# DualUSB2_0_HDR.net
KiCad netlist of a schematic drawn in Altium Designer
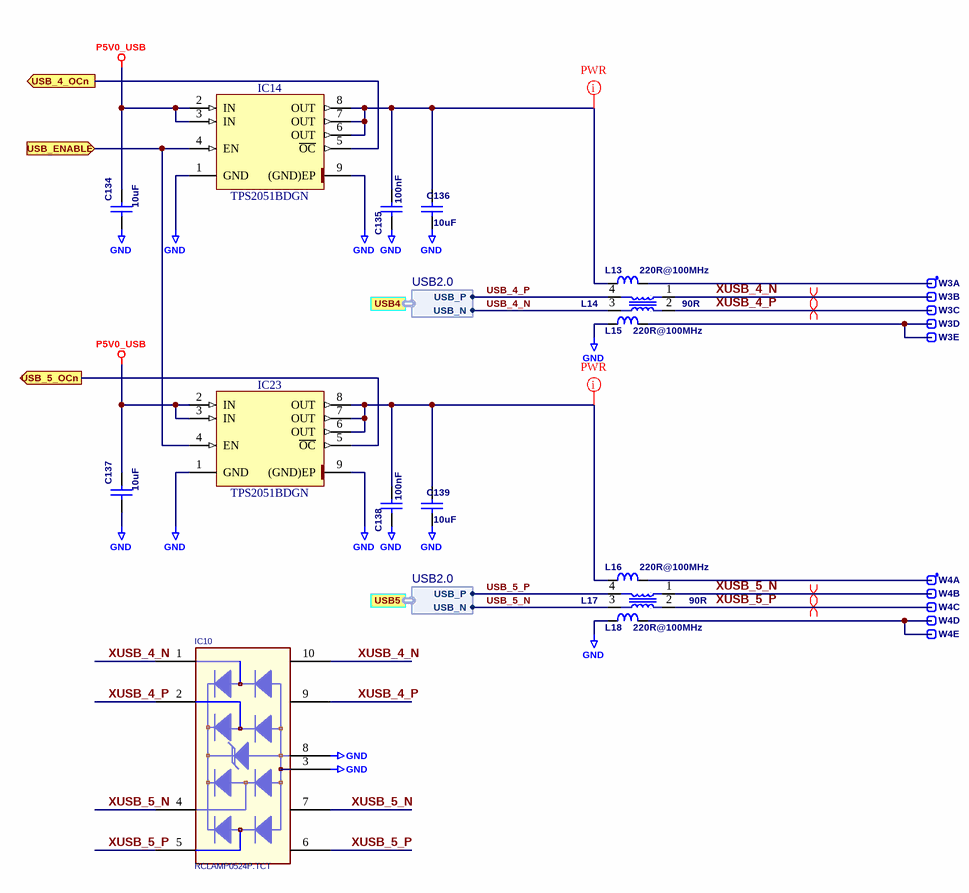
[diagram p0: DualUSB2.0_HDR.SchDoc]

(export (version "E")
  (design (tool "Eeschema 10.0.6"))
  (components
    (comp (ref "C134")
      (value "10uF")
      (footprint "CAPC2012X135N")
      (description "Non-polarised capacitor")
      (fields
        (field (name "PART NUMBER") "CC0805_10UF_10V_10%_X7R")
        (field (name "VOLTAGE") "10V")
        (field (name "AUTHOR") "CERN DEM JLC")
      )
      (libsource (lib "Capacitors") (part "Capacitor - non polarized"))
    )
    (comp (ref "C135")
      (value "100nF")
      (footprint "CAPC1005X55N")
      (description "Non-polarised capacitor")
      (fields
        (field (name "PART NUMBER") "CC0402_100NF_16V_10%_X7R")
        (field (name "VOLTAGE") "16V")
        (field (name "AUTHOR") "CERN DEM JLC")
      )
      (libsource (lib "Capacitors") (part "Capacitor - non polarized"))
    )
    (comp (ref "C136")
      (value "10uF")
      (footprint "CAPC2012X135N")
      (description "Non-polarised capacitor")
      (fields
        (field (name "PART NUMBER") "CC0805_10UF_10V_10%_X7R")
        (field (name "VOLTAGE") "10V")
        (field (name "AUTHOR") "CERN DEM JLC")
      )
      (libsource (lib "Capacitors") (part "Capacitor - non polarized"))
    )
    (comp (ref "C137")
      (value "10uF")
      (footprint "CAPC2012X135N")
      (description "Non-polarised capacitor")
      (fields
        (field (name "PART NUMBER") "CC0805_10UF_10V_10%_X7R")
        (field (name "VOLTAGE") "10V")
        (field (name "AUTHOR") "CERN DEM JLC")
      )
      (libsource (lib "Capacitors") (part "Capacitor - non polarized"))
    )
    (comp (ref "C138")
      (value "100nF")
      (footprint "CAPC1005X55N")
      (description "Non-polarised capacitor")
      (fields
        (field (name "PART NUMBER") "CC0402_100NF_16V_10%_X7R")
        (field (name "VOLTAGE") "16V")
        (field (name "AUTHOR") "CERN DEM JLC")
      )
      (libsource (lib "Capacitors") (part "Capacitor - non polarized"))
    )
    (comp (ref "C139")
      (value "10uF")
      (footprint "CAPC2012X135N")
      (description "Non-polarised capacitor")
      (fields
        (field (name "PART NUMBER") "CC0805_10UF_10V_10%_X7R")
        (field (name "VOLTAGE") "10V")
        (field (name "AUTHOR") "CERN DEM JLC")
      )
      (libsource (lib "Capacitors") (part "Capacitor - non polarized"))
    )
    (comp (ref "IC10")
      (value "RCLAMP0524P.TCT")
      (description "DIODE,RCLAMP0524P,SEMTECH")
      (libsource (lib "LIBRARY_SCH") (part "D_TVS_RCLAMP0524P"))
    )
    (comp (ref "IC14")
      (value "TPS2051BDGN")
      (footprint "SOP65P490X110-9N-R157X189")
      (description "One Channel, Current-Limited, Power-Distribution Switches")
      (fields (field (name "MANUFACTURER") "TEXAS INSTRUMENTS") (field (name "AUTHOR") "CERN DEM BC"))
      (libsource (lib "ICs And Semiconductors") (part "TPS2051BDGN"))
    )
    (comp (ref "IC23")
      (value "TPS2051BDGN")
      (footprint "SOP65P490X110-9N-R157X189")
      (description "One Channel, Current-Limited, Power-Distribution Switches")
      (fields (field (name "MANUFACTURER") "TEXAS INSTRUMENTS") (field (name "AUTHOR") "CERN DEM BC"))
      (libsource (lib "ICs And Semiconductors") (part "TPS2051BDGN"))
    )
    (comp (ref "L13")
      (value "220R@100MHz")
      (footprint "INDC2012X105N")
      (description "Inductor")
      (fields
        (field (name "PART NUMBER") "IND0805_MURATA_BLM21PG221SN1D")
        (field (name "POWER") "2A")
        (field (name "AUTHOR") "CERN DEM JLC")
      )
      (libsource (lib "Inductors & Transformers") (part "Inductor"))
    )
    (comp (ref "L14")
      (value "90R")
      (footprint "DLSCM0805")
      (description "Common Mode Choke 90R")
      (fields (field (name "Comment") "DLSCM0805-900M or DLW21SN900SQ2L"))
      (libsource (lib "LIBRARY_SCH") (part "L_CMC_DLSCM0805_90R"))
    )
    (comp (ref "L15")
      (value "220R@100MHz")
      (footprint "INDC2012X105N")
      (description "Inductor")
      (fields
        (field (name "PART NUMBER") "IND0805_MURATA_BLM21PG221SN1D")
        (field (name "POWER") "2A")
        (field (name "AUTHOR") "CERN DEM JLC")
      )
      (libsource (lib "Inductors & Transformers") (part "Inductor"))
    )
    (comp (ref "L16")
      (value "220R@100MHz")
      (footprint "INDC2012X105N")
      (description "Inductor")
      (fields
        (field (name "PART NUMBER") "IND0805_MURATA_BLM21PG221SN1D")
        (field (name "POWER") "2A")
        (field (name "AUTHOR") "CERN DEM JLC")
      )
      (libsource (lib "Inductors & Transformers") (part "Inductor"))
    )
    (comp (ref "L17")
      (value "90R")
      (footprint "DLSCM0805")
      (description "Common Mode Choke 90R")
      (fields (field (name "Comment") "DLSCM0805-900M or DLW21SN900SQ2L"))
      (libsource (lib "LIBRARY_SCH") (part "L_CMC_DLSCM0805_90R"))
    )
    (comp (ref "L18")
      (value "220R@100MHz")
      (footprint "INDC2012X105N")
      (description "Inductor")
      (fields
        (field (name "PART NUMBER") "IND0805_MURATA_BLM21PG221SN1D")
        (field (name "POWER") "2A")
        (field (name "AUTHOR") "CERN DEM JLC")
      )
      (libsource (lib "Inductors & Transformers") (part "Inductor"))
    )
    (comp (ref "W3")
      (value "Header 5")
      (footprint "SAMTEC_MTLW-105-07-L-S-250")
      (description "5 Mini Wire-Wrap Contact Strip Header")
      (fields
        (field (name "PART NUMBER") "SAMTEC_MTLW-105-07-L-S-250")
        (field (name "MANUFACTURER") "SAMTEC")
        (field (name "AUTHOR") "CERN DEM JLC")
      )
      (libsource (lib "Connectors") (part "Wire-Wrap Contact x5"))
    )
    (comp (ref "W4")
      (value "Header 5")
      (footprint "SAMTEC_MTLW-105-07-L-S-250")
      (description "5 Mini Wire-Wrap Contact Strip Header")
      (fields
        (field (name "PART NUMBER") "SAMTEC_MTLW-105-07-L-S-250")
        (field (name "MANUFACTURER") "SAMTEC")
        (field (name "AUTHOR") "CERN DEM JLC")
      )
      (libsource (lib "Connectors") (part "Wire-Wrap Contact x5"))
    )
  )
  (nets
    (net (code "2") (name "/USB_4_N") (class "Default")
      (node (ref "L14") (pin "3") (pinfunction "3_3") (pintype "passive"))
    )
    (net (code "3") (name "/USB_4_OCn") (class "Default")
      (node (ref "IC14") (pin "5") (pinfunction "~{OC}_5") (pintype "output"))
    )
    (net (code "4") (name "/USB_4_P") (class "Default")
      (node (ref "L14") (pin "4") (pinfunction "4_4") (pintype "passive"))
    )
    (net (code "5") (name "/USB_5_N") (class "Default")
      (node (ref "L17") (pin "3") (pinfunction "3_3") (pintype "passive"))
    )
    (net (code "6") (name "/USB_5_OCn") (class "Default")
      (node (ref "IC23") (pin "5") (pinfunction "~{OC}_5") (pintype "output"))
    )
    (net (code "7") (name "/USB_5_P") (class "Default")
      (node (ref "L17") (pin "4") (pinfunction "4_4") (pintype "passive"))
    )
    (net (code "8") (name "/USB_ENABLE") (class "Default")
      (node (ref "IC14") (pin "4") (pinfunction "EN_4") (pintype "input"))
      (node (ref "IC23") (pin "4") (pinfunction "EN_4") (pintype "input"))
    )
    (net (code "9") (name "/XUSB_4_N") (class "Default")
      (node (ref "IC10") (pin "1") (pinfunction "1_1") (pintype "passive"))
      (node (ref "IC10") (pin "10") (pinfunction "10_10") (pintype "passive"))
      (node (ref "L14") (pin "1") (pinfunction "1_1") (pintype "passive"))
      (node (ref "W3") (pin "2") (pinfunction "2_2") (pintype "bidirectional"))
    )
    (net (code "10") (name "/XUSB_4_P") (class "Default")
      (node (ref "IC10") (pin "2") (pinfunction "2_2") (pintype "passive"))
      (node (ref "IC10") (pin "9") (pinfunction "9_9") (pintype "passive"))
      (node (ref "L14") (pin "2") (pinfunction "2_2") (pintype "passive"))
      (node (ref "W3") (pin "3") (pinfunction "3_3") (pintype "bidirectional"))
    )
    (net (code "11") (name "/XUSB_5_N") (class "Default")
      (node (ref "IC10") (pin "4") (pinfunction "4_4") (pintype "passive"))
      (node (ref "IC10") (pin "7") (pinfunction "7_7") (pintype "passive"))
      (node (ref "L17") (pin "1") (pinfunction "1_1") (pintype "passive"))
      (node (ref "W4") (pin "2") (pinfunction "2_2") (pintype "bidirectional"))
    )
    (net (code "12") (name "/XUSB_5_P") (class "Default")
      (node (ref "IC10") (pin "5") (pinfunction "5_5") (pintype "passive"))
      (node (ref "IC10") (pin "6") (pinfunction "6_6") (pintype "passive"))
      (node (ref "L17") (pin "2") (pinfunction "2_2") (pintype "passive"))
      (node (ref "W4") (pin "3") (pinfunction "3_3") (pintype "bidirectional"))
    )
    (net (code "14") (name "GND") (class "Default")
      (node (ref "C134") (pin "1") (pinfunction "1_1") (pintype "passive"))
      (node (ref "C135") (pin "1") (pinfunction "1_1") (pintype "passive"))
      (node (ref "C136") (pin "1") (pinfunction "1_1") (pintype "passive"))
      (node (ref "C137") (pin "1") (pinfunction "1_1") (pintype "passive"))
      (node (ref "C138") (pin "1") (pinfunction "1_1") (pintype "passive"))
      (node (ref "C139") (pin "1") (pinfunction "1_1") (pintype "passive"))
      (node (ref "IC10") (pin "3") (pinfunction "3_3") (pintype "passive"))
      (node (ref "IC10") (pin "8") (pinfunction "8_8") (pintype "passive"))
      (node (ref "IC14") (pin "1") (pinfunction "GND_1") (pintype "power_in"))
      (node (ref "IC14") (pin "9") (pinfunction "(GND)EP_9") (pintype "power_in"))
      (node (ref "IC23") (pin "1") (pinfunction "GND_1") (pintype "power_in"))
      (node (ref "IC23") (pin "9") (pinfunction "(GND)EP_9") (pintype "power_in"))
      (node (ref "L15") (pin "1") (pinfunction "1_1") (pintype "passive"))
      (node (ref "L18") (pin "1") (pinfunction "1_1") (pintype "passive"))
    )
    (net (code "15") (name "Net-(C135-Pad2)") (class "Default")
      (node (ref "C135") (pin "2") (pinfunction "2_2") (pintype "passive"))
      (node (ref "C136") (pin "2") (pinfunction "2_2") (pintype "passive"))
      (node (ref "IC14") (pin "6") (pinfunction "OUT_6") (pintype "output"))
      (node (ref "IC14") (pin "7") (pinfunction "OUT_7") (pintype "output"))
      (node (ref "IC14") (pin "8") (pinfunction "OUT_8") (pintype "output"))
      (node (ref "L13") (pin "1") (pinfunction "1_1") (pintype "passive"))
    )
    (net (code "16") (name "Net-(C138-Pad2)") (class "Default")
      (node (ref "C138") (pin "2") (pinfunction "2_2") (pintype "passive"))
      (node (ref "C139") (pin "2") (pinfunction "2_2") (pintype "passive"))
      (node (ref "IC23") (pin "6") (pinfunction "OUT_6") (pintype "output"))
      (node (ref "IC23") (pin "7") (pinfunction "OUT_7") (pintype "output"))
      (node (ref "IC23") (pin "8") (pinfunction "OUT_8") (pintype "output"))
      (node (ref "L16") (pin "1") (pinfunction "1_1") (pintype "passive"))
    )
    (net (code "17") (name "Net-(L13-Pad2)") (class "Default")
      (node (ref "L13") (pin "2") (pinfunction "2_2") (pintype "passive"))
      (node (ref "W3") (pin "1") (pinfunction "1_1") (pintype "bidirectional"))
    )
    (net (code "18") (name "Net-(L15-Pad2)") (class "Default")
      (node (ref "L15") (pin "2") (pinfunction "2_2") (pintype "passive"))
      (node (ref "W3") (pin "4") (pinfunction "4_4") (pintype "bidirectional"))
      (node (ref "W3") (pin "5") (pinfunction "5_5") (pintype "bidirectional"))
    )
    (net (code "19") (name "Net-(L16-Pad2)") (class "Default")
      (node (ref "L16") (pin "2") (pinfunction "2_2") (pintype "passive"))
      (node (ref "W4") (pin "1") (pinfunction "1_1") (pintype "bidirectional"))
    )
    (net (code "20") (name "Net-(L18-Pad2)") (class "Default")
      (node (ref "L18") (pin "2") (pinfunction "2_2") (pintype "passive"))
      (node (ref "W4") (pin "4") (pinfunction "4_4") (pintype "bidirectional"))
      (node (ref "W4") (pin "5") (pinfunction "5_5") (pintype "bidirectional"))
    )
    (net (code "21") (name "P5V0_USB") (class "Default")
      (node (ref "C134") (pin "2") (pinfunction "2_2") (pintype "passive"))
      (node (ref "C137") (pin "2") (pinfunction "2_2") (pintype "passive"))
      (node (ref "IC14") (pin "2") (pinfunction "IN_2") (pintype "input"))
      (node (ref "IC14") (pin "3") (pinfunction "IN_3") (pintype "input"))
      (node (ref "IC23") (pin "2") (pinfunction "IN_2") (pintype "input"))
      (node (ref "IC23") (pin "3") (pinfunction "IN_3") (pintype "input"))
    )
  )
)
